# Sheet1.net
KiCad netlist of a schematic drawn in Altium Designer
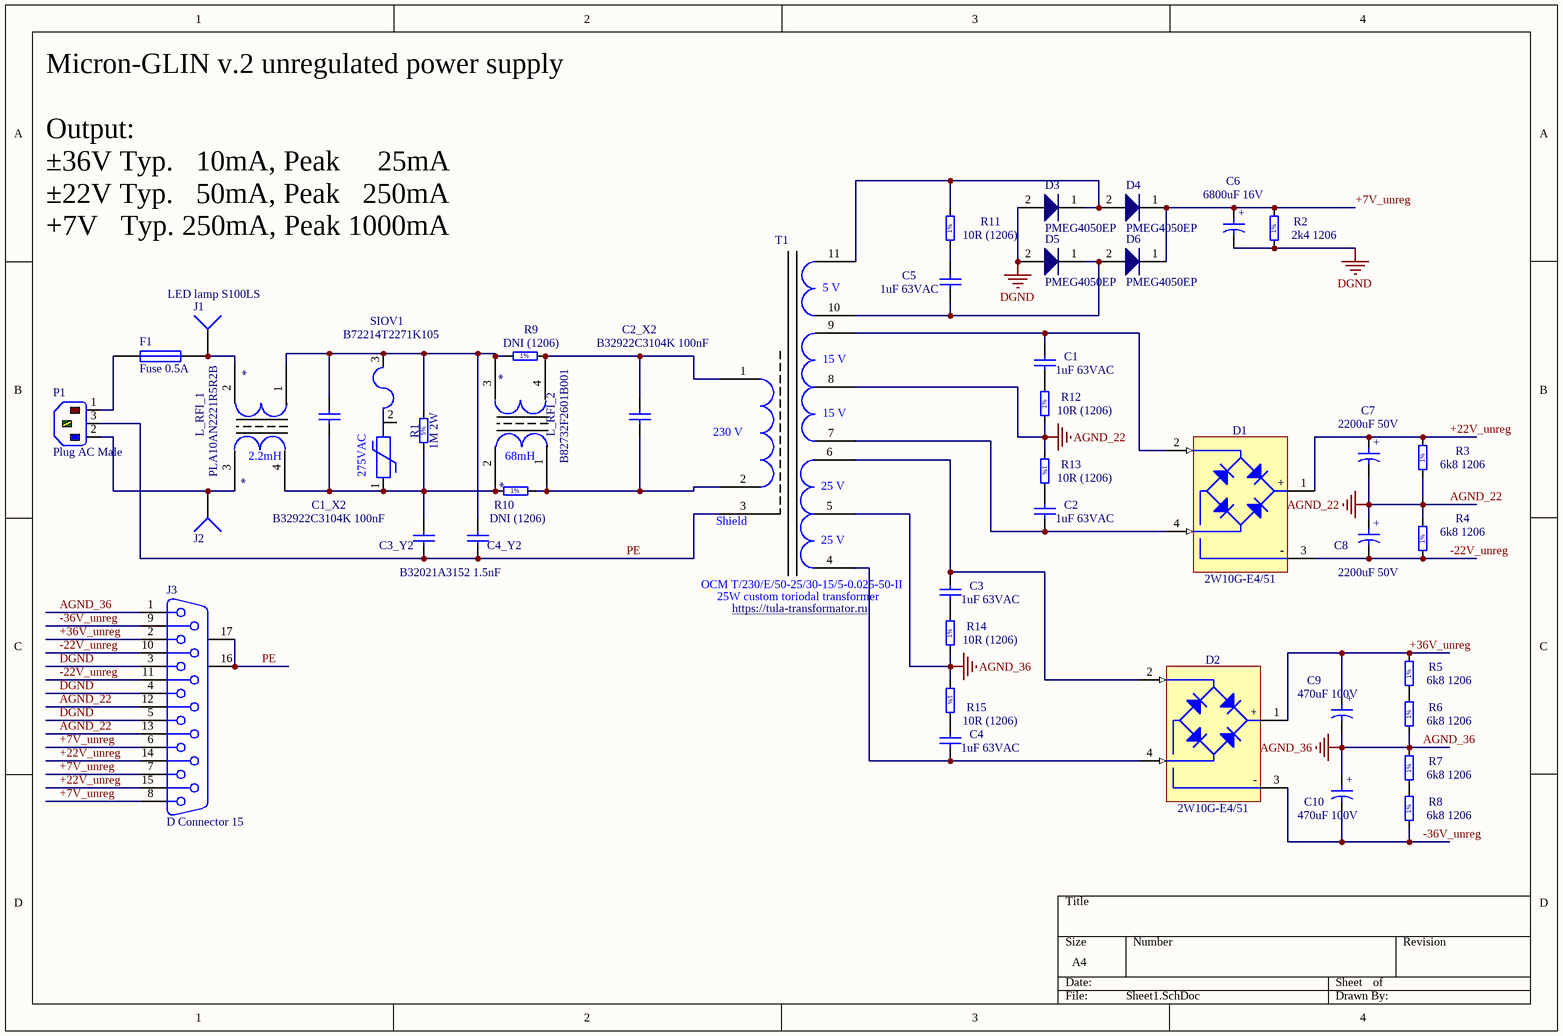
[diagram p0: Sheet1.SchDoc]

(export (version "E")
  (design (tool "Eeschema 10.0.6"))
  (components
    (comp (ref "C1")
      (value "1uF 63VAC")
      (footprint "B32522C1105")
      (description "Non-polarised capacitor")
      (fields
        (field (name "PART NUMBER") "CPPR_330NF_630V_5%_2250-1050X2650X1650")
        (field (name "VOLTAGE") "630VDC/250VAC")
        (field (name "AUTHOR") "CERN DEM JLC")
      )
      (libsource (lib "Capacitors") (part "Capacitor - non polarized"))
    )
    (comp (ref "C1_X2")
      (value "B32922C3104K 100nF")
      (footprint "B32922D3334K")
      (description "Non-polarised capacitor")
      (fields
        (field (name "PART NUMBER") "CPPR_330NF_630V_5%_2250-1050X2650X1650")
        (field (name "VOLTAGE") "630VDC/250VAC")
        (field (name "AUTHOR") "CERN DEM JLC")
      )
      (libsource (lib "Capacitors") (part "Capacitor - non polarized"))
    )
    (comp (ref "C2")
      (value "1uF 63VAC")
      (footprint "B32522C1105")
      (description "Non-polarised capacitor")
      (fields
        (field (name "PART NUMBER") "CPPR_330NF_630V_5%_2250-1050X2650X1650")
        (field (name "VOLTAGE") "630VDC/250VAC")
        (field (name "AUTHOR") "CERN DEM JLC")
      )
      (libsource (lib "Capacitors") (part "Capacitor - non polarized"))
    )
    (comp (ref "C2_X2")
      (value "B32922C3104K 100nF")
      (footprint "B32922D3334K")
      (description "Non-polarised capacitor")
      (fields
        (field (name "PART NUMBER") "CPPR_330NF_630V_5%_2250-1050X2650X1650")
        (field (name "VOLTAGE") "630VDC/250VAC")
        (field (name "AUTHOR") "CERN DEM JLC")
      )
      (libsource (lib "Capacitors") (part "Capacitor - non polarized"))
    )
    (comp (ref "C3")
      (value "1uF 63VAC")
      (footprint "B32522C1105")
      (description "Non-polarised capacitor")
      (fields
        (field (name "PART NUMBER") "CPPR_330NF_630V_5%_2250-1050X2650X1650")
        (field (name "VOLTAGE") "630VDC/250VAC")
        (field (name "AUTHOR") "CERN DEM JLC")
      )
      (libsource (lib "Capacitors") (part "Capacitor - non polarized"))
    )
    (comp (ref "C3_Y2")
      (value "B32021A3152 1.5nF")
      (footprint "B32021A3152")
      (description "Non-polarised capacitor")
      (fields
        (field (name "PART NUMBER") "CPPR_330NF_630V_5%_2250-1050X2650X1650")
        (field (name "VOLTAGE") "630VDC/250VAC")
        (field (name "AUTHOR") "CERN DEM JLC")
      )
      (libsource (lib "Capacitors") (part "Capacitor - non polarized"))
    )
    (comp (ref "C4")
      (value "1uF 63VAC")
      (footprint "B32522C1105")
      (description "Non-polarised capacitor")
      (fields
        (field (name "PART NUMBER") "CPPR_330NF_630V_5%_2250-1050X2650X1650")
        (field (name "VOLTAGE") "630VDC/250VAC")
        (field (name "AUTHOR") "CERN DEM JLC")
      )
      (libsource (lib "Capacitors") (part "Capacitor - non polarized"))
    )
    (comp (ref "C4_Y2")
      (value "B32021A3152 1.5nF")
      (footprint "B32021A3152")
      (description "Non-polarised capacitor")
      (fields
        (field (name "PART NUMBER") "CPPR_330NF_630V_5%_2250-1050X2650X1650")
        (field (name "VOLTAGE") "630VDC/250VAC")
        (field (name "AUTHOR") "CERN DEM JLC")
      )
      (libsource (lib "Capacitors") (part "Capacitor - non polarized"))
    )
    (comp (ref "C5")
      (value "1uF 63VAC")
      (footprint "B32522C1475")
      (description "Non-polarised capacitor")
      (fields
        (field (name "PART NUMBER") "CPPR_330NF_630V_5%_2250-1050X2650X1650")
        (field (name "VOLTAGE") "630VDC/250VAC")
        (field (name "AUTHOR") "CERN DEM JLC")
      )
      (libsource (lib "Capacitors") (part "Capacitor - non polarized"))
    )
    (comp (ref "C6")
      (value "6800uF 16V")
      (footprint "CAPPR750-1850X3750")
      (description "Polarised capacitor")
      (fields
        (field (name "PART NUMBER") "CAER_10000UF_16V_20%_CHEMI-CON_EKYB160ELL103MMP1S")
        (field (name "VOLTAGE") "16V")
        (field (name "AUTHOR") "CERN DEM JLC")
      )
      (libsource (lib "Capacitors") (part "Capacitor - polarized"))
    )
    (comp (ref "C7")
      (value "2200uF 50V")
      (footprint "CAPPR750-1850X3750")
      (description "Polarised capacitor")
      (fields
        (field (name "PART NUMBER") "CAER_10000UF_16V_20%_CHEMI-CON_EKYB160ELL103MMP1S")
        (field (name "VOLTAGE") "16V")
        (field (name "AUTHOR") "CERN DEM JLC")
      )
      (libsource (lib "Capacitors") (part "Capacitor - polarized"))
    )
    (comp (ref "C8")
      (value "2200uF 50V")
      (footprint "CAPPR750-1850X3750")
      (description "Polarised capacitor")
      (fields
        (field (name "PART NUMBER") "CAER_10000UF_16V_20%_CHEMI-CON_EKYB160ELL103MMP1S")
        (field (name "VOLTAGE") "16V")
        (field (name "AUTHOR") "CERN DEM JLC")
      )
      (libsource (lib "Capacitors") (part "Capacitor - polarized"))
    )
    (comp (ref "C9")
      (value "470uF 100V")
      (footprint "CAPPR750-1850X3750")
      (description "Polarised capacitor")
      (fields
        (field (name "PART NUMBER") "CAER_10000UF_16V_20%_CHEMI-CON_EKYB160ELL103MMP1S")
        (field (name "VOLTAGE") "16V")
        (field (name "AUTHOR") "CERN DEM JLC")
      )
      (libsource (lib "Capacitors") (part "Capacitor - polarized"))
    )
    (comp (ref "C10")
      (value "470uF 100V")
      (footprint "CAPPR750-1850X3750")
      (description "Polarised capacitor")
      (fields
        (field (name "PART NUMBER") "CAER_10000UF_16V_20%_CHEMI-CON_EKYB160ELL103MMP1S")
        (field (name "VOLTAGE") "16V")
        (field (name "AUTHOR") "CERN DEM JLC")
      )
      (libsource (lib "Capacitors") (part "Capacitor - polarized"))
    )
    (comp (ref "D1")
      (value "2W10G-E4/51")
      (footprint "VISHAY_WOG")
      (description "Bridge Rectifier 1+ 2AC 3- 4AC")
      (fields
        (field (name "PART NUMBER") "W005G-E4/51")
        (field (name "VOLTAGE") "50V")
        (field (name "AUTHOR") "CERN DEM JLC")
      )
      (libsource (lib "ICs And Semiconductors") (part "Bridge Rectifier 1+ 2AC 3- 4AC"))
    )
    (comp (ref "D2")
      (value "2W10G-E4/51")
      (footprint "VISHAY_WOG")
      (description "Bridge Rectifier 1+ 2AC 3- 4AC")
      (fields
        (field (name "PART NUMBER") "W005G-E4/51")
        (field (name "VOLTAGE") "50V")
        (field (name "AUTHOR") "CERN DEM JLC")
      )
      (libsource (lib "ICs And Semiconductors") (part "Bridge Rectifier 1+ 2AC 3- 4AC"))
    )
    (comp (ref "D3")
      (value "PMEG4050EP")
      (footprint "PMEG4050EP")
      (libsource (lib "My SCH library") (part "PMEG4050EP"))
    )
    (comp (ref "D4")
      (value "PMEG4050EP")
      (footprint "PMEG4050EP")
      (libsource (lib "My SCH library") (part "PMEG4050EP"))
    )
    (comp (ref "D5")
      (value "PMEG4050EP")
      (footprint "PMEG4050EP")
      (libsource (lib "My SCH library") (part "PMEG4050EP"))
    )
    (comp (ref "D6")
      (value "PMEG4050EP")
      (footprint "PMEG4050EP")
      (libsource (lib "My SCH library") (part "PMEG4050EP"))
    )
    (comp (ref "F1")
      (value "Fuse 0.5A")
      (footprint "FUSE")
      (description "Fuse")
      (fields (field (name "PUBLISHER") "Altium Limited"))
      (libsource (lib "Miscellaneous Devices") (part "Fuse 1"))
    )
    (comp (ref "J1")
      (value "Socket")
      (footprint "PIN1")
      (fields (field (name "PUBLISHER") "Altium Limited"))
      (libsource (lib "Miscellaneous Connectors") (part "Socket"))
    )
    (comp (ref "J2")
      (value "Socket")
      (footprint "PIN1")
      (fields (field (name "PUBLISHER") "Altium Limited"))
      (libsource (lib "Miscellaneous Connectors") (part "Socket"))
    )
    (comp (ref "J3")
      (value "D Connector 15")
      (footprint "DSUB1.385-2H15")
      (description "Receptacle Assembly, 15 Position, Right Angle")
      (fields (field (name "PUBLISHER") "Altium Limited"))
      (libsource (lib "Miscellaneous Connectors") (part "D Connector 15"))
    )
    (comp (ref "L_RFI_1")
      (value "PLA10AN2221R5R2B")
      (footprint "PLA10AN2221R5R2B")
      (libsource (lib "My SCH library") (part "PLA10AN2221R5R2B"))
    )
    (comp (ref "L_RFI_2")
      (value "B82732F2601B001")
      (footprint "B82732F")
      (libsource (lib "") (part "PLA10AN2221R5R2B_1"))
    )
    (comp (ref "P1")
      (value "Plug AC Male")
      (footprint "AS-205")
      (description "IEC Mains Power Inlet, EN60 320-1 C14 Class I Cold Condition, PC Flange Rear Mount, Chassis Plug")
      (fields (field (name "PUBLISHER") "Altium Limited"))
      (libsource (lib "Miscellaneous Connectors") (part "Plug AC Male"))
    )
    (comp (ref "R1")
      (value "1M 2W")
      (footprint "RES_TYCO_CFR200")
      (description "Resistor - 5%")
      (fields
        (field (name "PART NUMBER") "RCF_NO-VALUE_5%_2W_0-450PPM_TYCO_CFR200")
        (field (name "POWER") "2W")
        (field (name "AUTHOR") "CERN DEM JLC")
      )
      (libsource (lib "Resistors") (part "Resistor - 5%"))
    )
    (comp (ref "R2")
      (value "2k4 1206")
      (footprint "RESC3216X65N")
      (description "Resistor - 1%")
      (fields
        (field (name "PART NUMBER") "R1206_2K4_1%_0.25W_100PPM")
        (field (name "POWER") "0.25W")
        (field (name "AUTHOR") "CERN DEM JLC")
      )
      (libsource (lib "Resistors") (part "Resistor - 1%"))
    )
    (comp (ref "R3")
      (value "6k8 1206")
      (footprint "RESC3216X65N")
      (description "Resistor - 1%")
      (fields
        (field (name "PART NUMBER") "R1206_2K4_1%_0.25W_100PPM")
        (field (name "POWER") "0.25W")
        (field (name "AUTHOR") "CERN DEM JLC")
      )
      (libsource (lib "Resistors") (part "Resistor - 1%"))
    )
    (comp (ref "R4")
      (value "6k8 1206")
      (footprint "RESC3216X65N")
      (description "Resistor - 1%")
      (fields
        (field (name "PART NUMBER") "R1206_2K4_1%_0.25W_100PPM")
        (field (name "POWER") "0.25W")
        (field (name "AUTHOR") "CERN DEM JLC")
      )
      (libsource (lib "Resistors") (part "Resistor - 1%"))
    )
    (comp (ref "R5")
      (value "6k8 1206")
      (footprint "RESC3216X65N")
      (description "Resistor - 1%")
      (fields
        (field (name "PART NUMBER") "R1206_2K4_1%_0.25W_100PPM")
        (field (name "POWER") "0.25W")
        (field (name "AUTHOR") "CERN DEM JLC")
      )
      (libsource (lib "Resistors") (part "Resistor - 1%"))
    )
    (comp (ref "R6")
      (value "6k8 1206")
      (footprint "RESC3216X65N")
      (description "Resistor - 1%")
      (fields
        (field (name "PART NUMBER") "R1206_2K4_1%_0.25W_100PPM")
        (field (name "POWER") "0.25W")
        (field (name "AUTHOR") "CERN DEM JLC")
      )
      (libsource (lib "Resistors") (part "Resistor - 1%"))
    )
    (comp (ref "R7")
      (value "6k8 1206")
      (footprint "RESC3216X65N")
      (description "Resistor - 1%")
      (fields
        (field (name "PART NUMBER") "R1206_2K4_1%_0.25W_100PPM")
        (field (name "POWER") "0.25W")
        (field (name "AUTHOR") "CERN DEM JLC")
      )
      (libsource (lib "Resistors") (part "Resistor - 1%"))
    )
    (comp (ref "R8")
      (value "6k8 1206")
      (footprint "RESC3216X65N")
      (description "Resistor - 1%")
      (fields
        (field (name "PART NUMBER") "R1206_2K4_1%_0.25W_100PPM")
        (field (name "POWER") "0.25W")
        (field (name "AUTHOR") "CERN DEM JLC")
      )
      (libsource (lib "Resistors") (part "Resistor - 1%"))
    )
    (comp (ref "R9")
      (value "DNI (1206)")
      (footprint "RESC3216X65N")
      (description "Resistor - 1%")
      (fields
        (field (name "PART NUMBER") "R1206_2K4_1%_0.25W_100PPM")
        (field (name "POWER") "0.25W")
        (field (name "AUTHOR") "CERN DEM JLC")
      )
      (libsource (lib "Resistors") (part "Resistor - 1%"))
    )
    (comp (ref "R10")
      (value "DNI (1206)")
      (footprint "RESC3216X65N")
      (description "Resistor - 1%")
      (fields
        (field (name "PART NUMBER") "R1206_2K4_1%_0.25W_100PPM")
        (field (name "POWER") "0.25W")
        (field (name "AUTHOR") "CERN DEM JLC")
      )
      (libsource (lib "Resistors") (part "Resistor - 1%"))
    )
    (comp (ref "R11")
      (value "10R (1206)")
      (footprint "RESC3216X65N")
      (description "Resistor - 1%")
      (fields
        (field (name "PART NUMBER") "R1206_2K4_1%_0.25W_100PPM")
        (field (name "POWER") "0.25W")
        (field (name "AUTHOR") "CERN DEM JLC")
      )
      (libsource (lib "Resistors") (part "Resistor - 1%"))
    )
    (comp (ref "R12")
      (value "10R (1206)")
      (footprint "RESC3216X65N")
      (description "Resistor - 1%")
      (fields
        (field (name "PART NUMBER") "R1206_2K4_1%_0.25W_100PPM")
        (field (name "POWER") "0.25W")
        (field (name "AUTHOR") "CERN DEM JLC")
      )
      (libsource (lib "Resistors") (part "Resistor - 1%"))
    )
    (comp (ref "R13")
      (value "10R (1206)")
      (footprint "RESC3216X65N")
      (description "Resistor - 1%")
      (fields
        (field (name "PART NUMBER") "R1206_2K4_1%_0.25W_100PPM")
        (field (name "POWER") "0.25W")
        (field (name "AUTHOR") "CERN DEM JLC")
      )
      (libsource (lib "Resistors") (part "Resistor - 1%"))
    )
    (comp (ref "R14")
      (value "10R (1206)")
      (footprint "RESC3216X65N")
      (description "Resistor - 1%")
      (fields
        (field (name "PART NUMBER") "R1206_2K4_1%_0.25W_100PPM")
        (field (name "POWER") "0.25W")
        (field (name "AUTHOR") "CERN DEM JLC")
      )
      (libsource (lib "Resistors") (part "Resistor - 1%"))
    )
    (comp (ref "R15")
      (value "10R (1206)")
      (footprint "RESC3216X65N")
      (description "Resistor - 1%")
      (fields
        (field (name "PART NUMBER") "R1206_2K4_1%_0.25W_100PPM")
        (field (name "POWER") "0.25W")
        (field (name "AUTHOR") "CERN DEM JLC")
      )
      (libsource (lib "Resistors") (part "Resistor - 1%"))
    )
    (comp (ref "SIOV1")
      (value "B72214T2271K105")
      (footprint "B72214T2271K105")
      (fields (field (name "ORDER") "B72214T2271K105") (field (name "PUBLISHER") "Altium Limited"))
      (libsource (lib "My SCH library") (part "B72214T2271K105"))
    )
    (comp (ref "T1")
      (value "OCM T/230/E/50-25/30-15/5-0.025-50-II")
      (footprint "OCM T/230/E/50-25/30-15/5-0.025-50-II")
      (libsource (lib "My SCH library") (part "OCM T/230/E/50-25/30-15/5-0.025-50-II"))
    )
  )
  (nets
    (net (code "1") (name "/+7V_unreg") (class "Default")
      (node (ref "C6") (pin "1") (pinfunction "1_1") (pintype "passive"))
      (node (ref "D4") (pin "1") (pinfunction "1_1") (pintype "passive"))
      (node (ref "D6") (pin "1") (pinfunction "1_1") (pintype "passive"))
      (node (ref "J3") (pin "6") (pinfunction "6_6") (pintype "passive"))
      (node (ref "J3") (pin "7") (pinfunction "7_7") (pintype "passive"))
      (node (ref "J3") (pin "8") (pinfunction "8_8") (pintype "passive"))
      (node (ref "R2") (pin "2") (pinfunction "2_2") (pintype "passive"))
    )
    (net (code "2") (name "/+22V_unreg") (class "Default")
      (node (ref "C7") (pin "1") (pinfunction "1_1") (pintype "passive"))
      (node (ref "D1") (pin "1") (pinfunction "+_1") (pintype "power_in"))
      (node (ref "J3") (pin "14") (pinfunction "14_14") (pintype "passive"))
      (node (ref "J3") (pin "15") (pinfunction "15_15") (pintype "passive"))
      (node (ref "R3") (pin "2") (pinfunction "2_2") (pintype "passive"))
    )
    (net (code "3") (name "/+36V_unreg") (class "Default")
      (node (ref "C9") (pin "1") (pinfunction "1_1") (pintype "passive"))
      (node (ref "D2") (pin "1") (pinfunction "+_1") (pintype "power_in"))
      (node (ref "J3") (pin "2") (pinfunction "2_2") (pintype "passive"))
      (node (ref "R5") (pin "2") (pinfunction "2_2") (pintype "passive"))
    )
    (net (code "4") (name "/-22V_unreg") (class "Default")
      (node (ref "C8") (pin "2") (pinfunction "2_2") (pintype "passive"))
      (node (ref "D1") (pin "3") (pinfunction "-_3") (pintype "power_in"))
      (node (ref "J3") (pin "10") (pinfunction "10_10") (pintype "passive"))
      (node (ref "J3") (pin "11") (pinfunction "11_11") (pintype "passive"))
      (node (ref "R4") (pin "1") (pinfunction "1_1") (pintype "passive"))
    )
    (net (code "5") (name "/-36V_unreg") (class "Default")
      (node (ref "C10") (pin "2") (pinfunction "2_2") (pintype "passive"))
      (node (ref "D2") (pin "3") (pinfunction "-_3") (pintype "power_in"))
      (node (ref "J3") (pin "9") (pinfunction "9_9") (pintype "passive"))
      (node (ref "R8") (pin "1") (pinfunction "1_1") (pintype "passive"))
    )
    (net (code "6") (name "/PE") (class "Default")
      (node (ref "C3_Y2") (pin "1") (pinfunction "1_1") (pintype "passive"))
      (node (ref "C4_Y2") (pin "1") (pinfunction "1_1") (pintype "passive"))
      (node (ref "J3") (pin "16") (pinfunction "MH1_16") (pintype "passive"))
      (node (ref "J3") (pin "17") (pinfunction "MH2_17") (pintype "passive"))
      (node (ref "P1") (pin "3") (pinfunction "E_3") (pintype "power_in"))
      (node (ref "T1") (pin "3") (pinfunction "3_3") (pintype "passive"))
    )
    (net (code "7") (name "AGND_22") (class "Default")
      (node (ref "C7") (pin "2") (pinfunction "2_2") (pintype "passive"))
      (node (ref "C8") (pin "1") (pinfunction "1_1") (pintype "passive"))
      (node (ref "J3") (pin "12") (pinfunction "12_12") (pintype "passive"))
      (node (ref "J3") (pin "13") (pinfunction "13_13") (pintype "passive"))
      (node (ref "R12") (pin "1") (pinfunction "1_1") (pintype "passive"))
      (node (ref "R13") (pin "1") (pinfunction "1_1") (pintype "passive"))
      (node (ref "R3") (pin "1") (pinfunction "1_1") (pintype "passive"))
      (node (ref "R4") (pin "2") (pinfunction "2_2") (pintype "passive"))
      (node (ref "T1") (pin "8") (pinfunction "8_8") (pintype "passive"))
    )
    (net (code "8") (name "AGND_36") (class "Default")
      (node (ref "C10") (pin "1") (pinfunction "1_1") (pintype "passive"))
      (node (ref "C9") (pin "2") (pinfunction "2_2") (pintype "passive"))
      (node (ref "J3") (pin "1") (pinfunction "1_1") (pintype "passive"))
      (node (ref "R14") (pin "1") (pinfunction "1_1") (pintype "passive"))
      (node (ref "R15") (pin "1") (pinfunction "1_1") (pintype "passive"))
      (node (ref "R6") (pin "1") (pinfunction "1_1") (pintype "passive"))
      (node (ref "R7") (pin "2") (pinfunction "2_2") (pintype "passive"))
      (node (ref "T1") (pin "5") (pinfunction "5_5") (pintype "passive"))
    )
    (net (code "9") (name "DGND") (class "Default")
      (node (ref "C6") (pin "2") (pinfunction "2_2") (pintype "passive"))
      (node (ref "D3") (pin "2") (pinfunction "2_2") (pintype "passive"))
      (node (ref "D5") (pin "2") (pinfunction "2_2") (pintype "passive"))
      (node (ref "J3") (pin "3") (pinfunction "3_3") (pintype "passive"))
      (node (ref "J3") (pin "4") (pinfunction "4_4") (pintype "passive"))
      (node (ref "J3") (pin "5") (pinfunction "5_5") (pintype "passive"))
      (node (ref "R2") (pin "1") (pinfunction "1_1") (pintype "passive"))
    )
    (net (code "10") (name "Net-(C1-Pad1)") (class "Default")
      (node (ref "C1") (pin "1") (pinfunction "1_1") (pintype "passive"))
      (node (ref "R12") (pin "2") (pinfunction "2_2") (pintype "passive"))
    )
    (net (code "11") (name "Net-(C1-Pad2)") (class "Default")
      (node (ref "C1") (pin "2") (pinfunction "2_2") (pintype "passive"))
      (node (ref "D1") (pin "2") (pinfunction "AC_2") (pintype "input"))
      (node (ref "T1") (pin "9") (pinfunction "9_9") (pintype "passive"))
    )
    (net (code "12") (name "Net-(C1_X2-Pad1)") (class "Default")
      (node (ref "C1_X2") (pin "1") (pinfunction "1_1") (pintype "passive"))
      (node (ref "C3_Y2") (pin "2") (pinfunction "2_2") (pintype "passive"))
      (node (ref "L_RFI_1") (pin "4") (pinfunction "4_4") (pintype "passive"))
      (node (ref "L_RFI_2") (pin "2") (pinfunction "2_2") (pintype "passive"))
      (node (ref "R1") (pin "1") (pinfunction "1_1") (pintype "passive"))
      (node (ref "R10") (pin "1") (pinfunction "1_1") (pintype "passive"))
      (node (ref "SIOV1") (pin "1") (pinfunction "1_1") (pintype "passive"))
    )
    (net (code "13") (name "Net-(C1_X2-Pad2)") (class "Default")
      (node (ref "C1_X2") (pin "2") (pinfunction "2_2") (pintype "passive"))
      (node (ref "C4_Y2") (pin "2") (pinfunction "2_2") (pintype "passive"))
      (node (ref "L_RFI_1") (pin "1") (pinfunction "1_1") (pintype "passive"))
      (node (ref "L_RFI_2") (pin "3") (pinfunction "3_3") (pintype "passive"))
      (node (ref "R1") (pin "2") (pinfunction "2_2") (pintype "passive"))
      (node (ref "R9") (pin "1") (pinfunction "1_1") (pintype "passive"))
      (node (ref "SIOV1") (pin "3") (pinfunction "3_3") (pintype "passive"))
    )
    (net (code "14") (name "Net-(C2-Pad1)") (class "Default")
      (node (ref "C2") (pin "1") (pinfunction "1_1") (pintype "passive"))
      (node (ref "D1") (pin "4") (pinfunction "AC_4") (pintype "input"))
      (node (ref "T1") (pin "7") (pinfunction "8_7") (pintype "passive"))
    )
    (net (code "15") (name "Net-(C2-Pad2)") (class "Default")
      (node (ref "C2") (pin "2") (pinfunction "2_2") (pintype "passive"))
      (node (ref "R13") (pin "2") (pinfunction "2_2") (pintype "passive"))
    )
    (net (code "16") (name "Net-(C2_X2-Pad1)") (class "Default")
      (node (ref "C2_X2") (pin "1") (pinfunction "1_1") (pintype "passive"))
      (node (ref "L_RFI_2") (pin "1") (pinfunction "1_1") (pintype "passive"))
      (node (ref "R10") (pin "2") (pinfunction "2_2") (pintype "passive"))
      (node (ref "T1") (pin "2") (pintype "passive"))
    )
    (net (code "17") (name "Net-(C2_X2-Pad2)") (class "Default")
      (node (ref "C2_X2") (pin "2") (pinfunction "2_2") (pintype "passive"))
      (node (ref "L_RFI_2") (pin "4") (pinfunction "4_4") (pintype "passive"))
      (node (ref "R9") (pin "2") (pinfunction "2_2") (pintype "passive"))
      (node (ref "T1") (pin "1") (pinfunction "1_1") (pintype "passive"))
    )
    (net (code "18") (name "Net-(C3-Pad1)") (class "Default")
      (node (ref "C3") (pin "1") (pinfunction "1_1") (pintype "passive"))
      (node (ref "R14") (pin "2") (pinfunction "2_2") (pintype "passive"))
    )
    (net (code "19") (name "Net-(C3-Pad2)") (class "Default")
      (node (ref "C3") (pin "2") (pinfunction "2_2") (pintype "passive"))
      (node (ref "D2") (pin "2") (pinfunction "AC_2") (pintype "input"))
      (node (ref "T1") (pin "6") (pinfunction "6_6") (pintype "passive"))
    )
    (net (code "20") (name "Net-(C4-Pad1)") (class "Default")
      (node (ref "C4") (pin "1") (pinfunction "1_1") (pintype "passive"))
      (node (ref "D2") (pin "4") (pinfunction "AC_4") (pintype "input"))
      (node (ref "T1") (pin "4") (pinfunction "4_4") (pintype "passive"))
    )
    (net (code "21") (name "Net-(C4-Pad2)") (class "Default")
      (node (ref "C4") (pin "2") (pinfunction "2_2") (pintype "passive"))
      (node (ref "R15") (pin "2") (pinfunction "2_2") (pintype "passive"))
    )
    (net (code "22") (name "Net-(C5-Pad1)") (class "Default")
      (node (ref "C5") (pin "1") (pinfunction "1_1") (pintype "passive"))
      (node (ref "D5") (pin "1") (pinfunction "1_1") (pintype "passive"))
      (node (ref "D6") (pin "2") (pinfunction "2_2") (pintype "passive"))
      (node (ref "T1") (pin "10") (pinfunction "5_10") (pintype "passive"))
    )
    (net (code "23") (name "Net-(C5-Pad2)") (class "Default")
      (node (ref "C5") (pin "2") (pinfunction "2_2") (pintype "passive"))
      (node (ref "R11") (pin "1") (pinfunction "1_1") (pintype "passive"))
    )
    (net (code "24") (name "Net-(D3-Pad1)") (class "Default")
      (node (ref "D3") (pin "1") (pinfunction "1_1") (pintype "passive"))
      (node (ref "D4") (pin "2") (pinfunction "2_2") (pintype "passive"))
      (node (ref "R11") (pin "2") (pinfunction "2_2") (pintype "passive"))
      (node (ref "T1") (pin "11") (pinfunction "11_11") (pintype "passive"))
    )
    (net (code "25") (name "Net-(F1-Pad2)") (class "Default")
      (node (ref "F1") (pin "2") (pinfunction "2_2") (pintype "passive"))
      (node (ref "J1") (pin "1") (pinfunction "1_1") (pintype "passive"))
      (node (ref "L_RFI_1") (pin "2") (pinfunction "2_2") (pintype "passive"))
    )
    (net (code "26") (name "Net-(P1-L)") (class "Default")
      (node (ref "F1") (pin "1") (pinfunction "1_1") (pintype "passive"))
      (node (ref "P1") (pin "1") (pinfunction "L_1") (pintype "power_in"))
    )
    (net (code "27") (name "Net-(P1-N)") (class "Default")
      (node (ref "J2") (pin "1") (pinfunction "1_1") (pintype "passive"))
      (node (ref "L_RFI_1") (pin "3") (pinfunction "3_3") (pintype "passive"))
      (node (ref "P1") (pin "2") (pinfunction "N_2") (pintype "power_in"))
    )
    (net (code "28") (name "Net-(R5-Pad1)") (class "Default")
      (node (ref "R5") (pin "1") (pinfunction "1_1") (pintype "passive"))
      (node (ref "R6") (pin "2") (pinfunction "2_2") (pintype "passive"))
    )
    (net (code "29") (name "Net-(R7-Pad1)") (class "Default")
      (node (ref "R7") (pin "1") (pinfunction "1_1") (pintype "passive"))
      (node (ref "R8") (pin "2") (pinfunction "2_2") (pintype "passive"))
    )
    (net (code "30") (name "unconnected-(SIOV1-Pad2)") (class "Default")
      (node (ref "SIOV1") (pin "2") (pinfunction "2_2") (pintype "passive"))
    )
  )
)
